# 2x_Rollo_APP_TS_v0_1.net
KiCad netlist of a schematic drawn in EAGLE
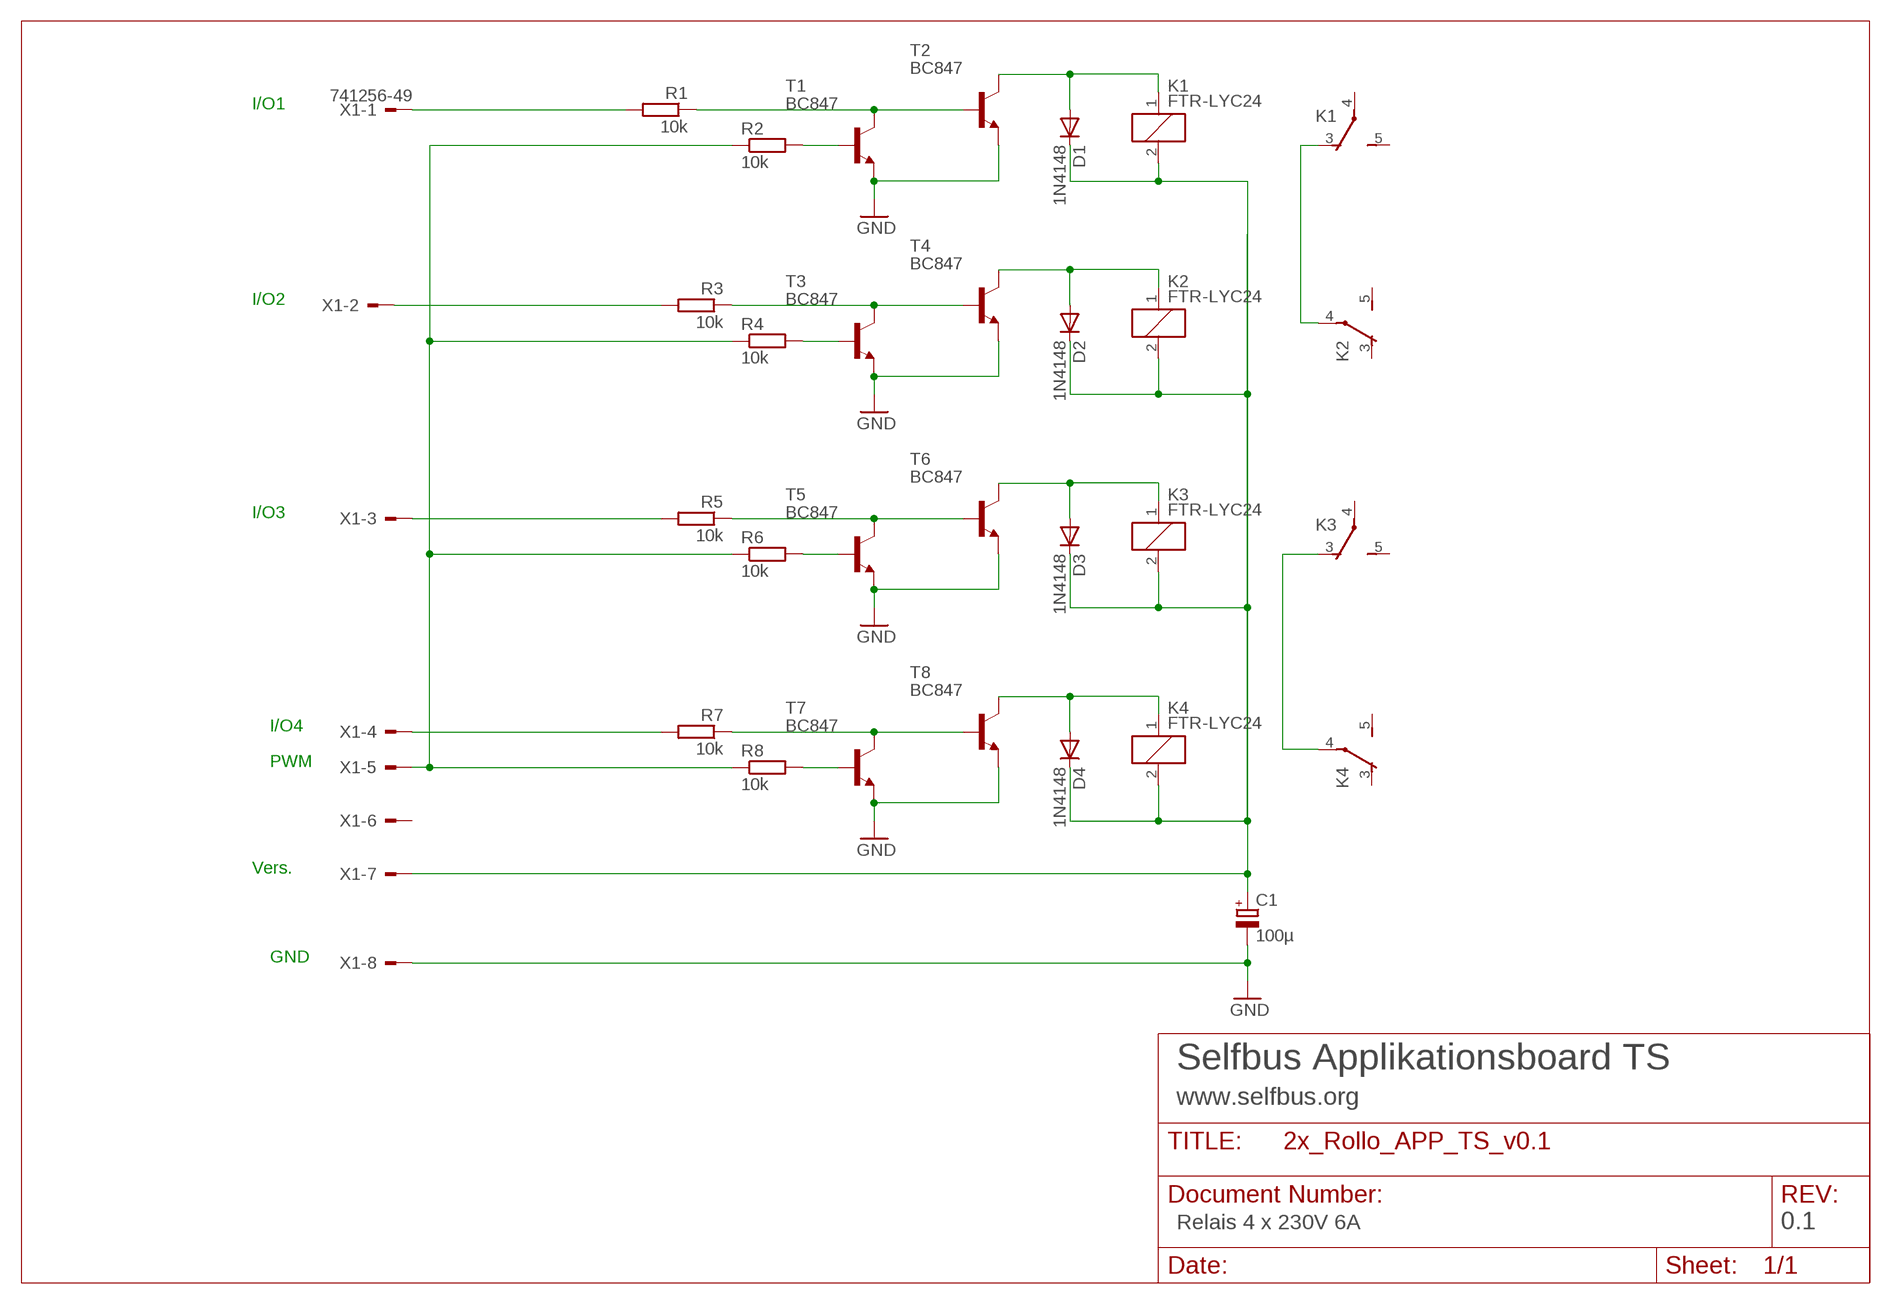
[diagram p0: schematic, sheet 1]

(export (version "E")
  (design (tool "Eeschema 10.0.6"))
  (components
    (comp (ref "C1")
      (value "100µ")
      (footprint "eagle-import:E2,5-6")
      (libsource (lib "eagle-import") (part "CPOL-EUE2.5-6"))
    )
    (comp (ref "D1")
      (value "1N4148")
      (footprint "eagle-import:MINIMELF")
      (libsource (lib "eagle-import") (part "DIODE-MINIMELF"))
    )
    (comp (ref "D2")
      (value "1N4148")
      (footprint "eagle-import:MINIMELF")
      (libsource (lib "eagle-import") (part "DIODE-MINIMELF"))
    )
    (comp (ref "D3")
      (value "1N4148")
      (footprint "eagle-import:MINIMELF")
      (libsource (lib "eagle-import") (part "DIODE-MINIMELF"))
    )
    (comp (ref "D4")
      (value "1N4148")
      (footprint "eagle-import:MINIMELF")
      (libsource (lib "eagle-import") (part "DIODE-MINIMELF"))
    )
    (comp (ref "K1")
      (value "FTR-LYC24")
      (footprint "eagle-import:FTR-LYC")
      (libsource (lib "eagle-import") (part "FTR-LYC24"))
    )
    (comp (ref "K2")
      (value "FTR-LYC24")
      (footprint "eagle-import:FTR-LYC")
      (libsource (lib "eagle-import") (part "FTR-LYC24"))
    )
    (comp (ref "K3")
      (value "FTR-LYC24")
      (footprint "eagle-import:FTR-LYC")
      (libsource (lib "eagle-import") (part "FTR-LYC24"))
    )
    (comp (ref "K4")
      (value "FTR-LYC24")
      (footprint "eagle-import:FTR-LYC")
      (libsource (lib "eagle-import") (part "FTR-LYC24"))
    )
    (comp (ref "R1")
      (value "10k")
      (footprint "eagle-import:M1206")
      (libsource (lib "eagle-import") (part "R-EU_M1206"))
    )
    (comp (ref "R2")
      (value "10k")
      (footprint "eagle-import:M1206")
      (libsource (lib "eagle-import") (part "R-EU_M1206"))
    )
    (comp (ref "R3")
      (value "10k")
      (footprint "eagle-import:M1206")
      (libsource (lib "eagle-import") (part "R-EU_M1206"))
    )
    (comp (ref "R4")
      (value "10k")
      (footprint "eagle-import:M1206")
      (libsource (lib "eagle-import") (part "R-EU_M1206"))
    )
    (comp (ref "R5")
      (value "10k")
      (footprint "eagle-import:M1206")
      (libsource (lib "eagle-import") (part "R-EU_M1206"))
    )
    (comp (ref "R6")
      (value "10k")
      (footprint "eagle-import:M1206")
      (libsource (lib "eagle-import") (part "R-EU_M1206"))
    )
    (comp (ref "R7")
      (value "10k")
      (footprint "eagle-import:M1206")
      (libsource (lib "eagle-import") (part "R-EU_M1206"))
    )
    (comp (ref "R8")
      (value "10k")
      (footprint "eagle-import:M1206")
      (libsource (lib "eagle-import") (part "R-EU_M1206"))
    )
    (comp (ref "T1")
      (value "BC847")
      (footprint "eagle-import:SOT23")
      (libsource (lib "eagle-import") (part "BC847"))
    )
    (comp (ref "T2")
      (value "BC847")
      (footprint "eagle-import:SOT23")
      (libsource (lib "eagle-import") (part "BC847"))
    )
    (comp (ref "T3")
      (value "BC847")
      (footprint "eagle-import:SOT23")
      (libsource (lib "eagle-import") (part "BC847"))
    )
    (comp (ref "T4")
      (value "BC847")
      (footprint "eagle-import:SOT23")
      (libsource (lib "eagle-import") (part "BC847"))
    )
    (comp (ref "T5")
      (value "BC847")
      (footprint "eagle-import:SOT23")
      (libsource (lib "eagle-import") (part "BC847"))
    )
    (comp (ref "T6")
      (value "BC847")
      (footprint "eagle-import:SOT23")
      (libsource (lib "eagle-import") (part "BC847"))
    )
    (comp (ref "T7")
      (value "BC847")
      (footprint "eagle-import:SOT23")
      (libsource (lib "eagle-import") (part "BC847"))
    )
    (comp (ref "T8")
      (value "BC847")
      (footprint "eagle-import:SOT23")
      (libsource (lib "eagle-import") (part "BC847"))
    )
    (comp (ref "X1")
      (value "741256-49")
      (footprint "eagle-import:741256-49")
      (libsource (lib "eagle-import") (part "741256-49"))
    )
  )
  (nets
    (net (code "1") (name "GND") (class "Default")
      (node (ref "C1") (pin "-") (pinfunction "-_-") (pintype "passive"))
      (node (ref "T1") (pin "2") (pinfunction "E_2") (pintype "passive"))
      (node (ref "T2") (pin "2") (pinfunction "E_2") (pintype "passive"))
      (node (ref "T3") (pin "2") (pinfunction "E_2") (pintype "passive"))
      (node (ref "T4") (pin "2") (pinfunction "E_2") (pintype "passive"))
      (node (ref "T5") (pin "2") (pinfunction "E_2") (pintype "passive"))
      (node (ref "T6") (pin "2") (pinfunction "E_2") (pintype "passive"))
      (node (ref "T7") (pin "2") (pinfunction "E_2") (pintype "passive"))
      (node (ref "T8") (pin "2") (pinfunction "E_2") (pintype "passive"))
      (node (ref "X1") (pin "8") (pinfunction "KL_8") (pintype "passive"))
    )
    (net (code "2") (name "Net-(K1A-O)") (class "Default")
      (node (ref "K1") (pin "3") (pinfunction "O_3") (pintype "passive"))
      (node (ref "K2") (pin "4") (pinfunction "P_4") (pintype "passive"))
    )
    (net (code "3") (name "Net-(K3A-O)") (class "Default")
      (node (ref "K3") (pin "3") (pinfunction "O_3") (pintype "passive"))
      (node (ref "K4") (pin "4") (pinfunction "P_4") (pintype "passive"))
    )
    (net (code "4") (name "Net-(T1-B)") (class "Default")
      (node (ref "R2") (pin "2") (pinfunction "2_2") (pintype "passive"))
      (node (ref "T1") (pin "1") (pinfunction "B_1") (pintype "passive"))
    )
    (net (code "5") (name "Net-(T1-C)") (class "Default")
      (node (ref "R1") (pin "1") (pinfunction "1_1") (pintype "passive"))
      (node (ref "T1") (pin "3") (pinfunction "C_3") (pintype "passive"))
      (node (ref "T2") (pin "1") (pinfunction "B_1") (pintype "passive"))
    )
    (net (code "6") (name "Net-(T2-C)") (class "Default")
      (node (ref "D1") (pin "A") (pinfunction "A_A") (pintype "passive"))
      (node (ref "K1") (pin "1") (pinfunction "1_1") (pintype "passive"))
      (node (ref "T2") (pin "3") (pinfunction "C_3") (pintype "passive"))
    )
    (net (code "7") (name "Net-(T3-B)") (class "Default")
      (node (ref "R4") (pin "2") (pinfunction "2_2") (pintype "passive"))
      (node (ref "T3") (pin "1") (pinfunction "B_1") (pintype "passive"))
    )
    (net (code "8") (name "Net-(T3-C)") (class "Default")
      (node (ref "R3") (pin "1") (pinfunction "1_1") (pintype "passive"))
      (node (ref "T3") (pin "3") (pinfunction "C_3") (pintype "passive"))
      (node (ref "T4") (pin "1") (pinfunction "B_1") (pintype "passive"))
    )
    (net (code "9") (name "Net-(T4-C)") (class "Default")
      (node (ref "D2") (pin "A") (pinfunction "A_A") (pintype "passive"))
      (node (ref "K2") (pin "1") (pinfunction "1_1") (pintype "passive"))
      (node (ref "T4") (pin "3") (pinfunction "C_3") (pintype "passive"))
    )
    (net (code "10") (name "Net-(T5-B)") (class "Default")
      (node (ref "R6") (pin "2") (pinfunction "2_2") (pintype "passive"))
      (node (ref "T5") (pin "1") (pinfunction "B_1") (pintype "passive"))
    )
    (net (code "11") (name "Net-(T5-C)") (class "Default")
      (node (ref "R5") (pin "1") (pinfunction "1_1") (pintype "passive"))
      (node (ref "T5") (pin "3") (pinfunction "C_3") (pintype "passive"))
      (node (ref "T6") (pin "1") (pinfunction "B_1") (pintype "passive"))
    )
    (net (code "12") (name "Net-(T6-C)") (class "Default")
      (node (ref "D3") (pin "A") (pinfunction "A_A") (pintype "passive"))
      (node (ref "K3") (pin "1") (pinfunction "1_1") (pintype "passive"))
      (node (ref "T6") (pin "3") (pinfunction "C_3") (pintype "passive"))
    )
    (net (code "13") (name "Net-(T7-B)") (class "Default")
      (node (ref "R8") (pin "2") (pinfunction "2_2") (pintype "passive"))
      (node (ref "T7") (pin "1") (pinfunction "B_1") (pintype "passive"))
    )
    (net (code "14") (name "Net-(T7-C)") (class "Default")
      (node (ref "R7") (pin "1") (pinfunction "1_1") (pintype "passive"))
      (node (ref "T7") (pin "3") (pinfunction "C_3") (pintype "passive"))
      (node (ref "T8") (pin "1") (pinfunction "B_1") (pintype "passive"))
    )
    (net (code "15") (name "Net-(T8-C)") (class "Default")
      (node (ref "D4") (pin "A") (pinfunction "A_A") (pintype "passive"))
      (node (ref "K4") (pin "1") (pinfunction "1_1") (pintype "passive"))
      (node (ref "T8") (pin "3") (pinfunction "C_3") (pintype "passive"))
    )
    (net (code "16") (name "Net-(X1A-KL)") (class "Default")
      (node (ref "R1") (pin "2") (pinfunction "2_2") (pintype "passive"))
      (node (ref "X1") (pin "1") (pinfunction "KL_1") (pintype "passive"))
    )
    (net (code "17") (name "Net-(X1B-KL)") (class "Default")
      (node (ref "R3") (pin "2") (pinfunction "2_2") (pintype "passive"))
      (node (ref "X1") (pin "2") (pinfunction "KL_2") (pintype "passive"))
    )
    (net (code "18") (name "Net-(X1C-KL)") (class "Default")
      (node (ref "R5") (pin "2") (pinfunction "2_2") (pintype "passive"))
      (node (ref "X1") (pin "3") (pinfunction "KL_3") (pintype "passive"))
    )
    (net (code "19") (name "Net-(X1D-KL)") (class "Default")
      (node (ref "R7") (pin "2") (pinfunction "2_2") (pintype "passive"))
      (node (ref "X1") (pin "4") (pinfunction "KL_4") (pintype "passive"))
    )
    (net (code "20") (name "Net-(X1E-KL)") (class "Default")
      (node (ref "R2") (pin "1") (pinfunction "1_1") (pintype "passive"))
      (node (ref "R4") (pin "1") (pinfunction "1_1") (pintype "passive"))
      (node (ref "R6") (pin "1") (pinfunction "1_1") (pintype "passive"))
      (node (ref "R8") (pin "1") (pinfunction "1_1") (pintype "passive"))
      (node (ref "X1") (pin "5") (pinfunction "KL_5") (pintype "passive"))
    )
    (net (code "21") (name "Net-(X1G-KL)") (class "Default")
      (node (ref "C1") (pin "+") (pinfunction "+_+") (pintype "passive"))
      (node (ref "D1") (pin "C") (pinfunction "C_C") (pintype "passive"))
      (node (ref "D2") (pin "C") (pinfunction "C_C") (pintype "passive"))
      (node (ref "D3") (pin "C") (pinfunction "C_C") (pintype "passive"))
      (node (ref "D4") (pin "C") (pinfunction "C_C") (pintype "passive"))
      (node (ref "K1") (pin "2") (pinfunction "2_2") (pintype "passive"))
      (node (ref "K2") (pin "2") (pinfunction "2_2") (pintype "passive"))
      (node (ref "K3") (pin "2") (pinfunction "2_2") (pintype "passive"))
      (node (ref "K4") (pin "2") (pinfunction "2_2") (pintype "passive"))
      (node (ref "X1") (pin "7") (pinfunction "KL_7") (pintype "passive"))
    )
    (net (code "22") (name "unconnected-(K1A-P-Pad4)") (class "Default")
      (node (ref "K1") (pin "4") (pinfunction "P_4") (pintype "passive"))
    )
    (net (code "23") (name "unconnected-(K1A-S-Pad5)") (class "Default")
      (node (ref "K1") (pin "5") (pinfunction "S_5") (pintype "passive"))
    )
    (net (code "24") (name "unconnected-(K2A-O-Pad3)") (class "Default")
      (node (ref "K2") (pin "3") (pinfunction "O_3") (pintype "passive"))
    )
    (net (code "25") (name "unconnected-(K2A-S-Pad5)") (class "Default")
      (node (ref "K2") (pin "5") (pinfunction "S_5") (pintype "passive"))
    )
    (net (code "26") (name "unconnected-(K3A-P-Pad4)") (class "Default")
      (node (ref "K3") (pin "4") (pinfunction "P_4") (pintype "passive"))
    )
    (net (code "27") (name "unconnected-(K3A-S-Pad5)") (class "Default")
      (node (ref "K3") (pin "5") (pinfunction "S_5") (pintype "passive"))
    )
    (net (code "28") (name "unconnected-(K4A-O-Pad3)") (class "Default")
      (node (ref "K4") (pin "3") (pinfunction "O_3") (pintype "passive"))
    )
    (net (code "29") (name "unconnected-(K4A-S-Pad5)") (class "Default")
      (node (ref "K4") (pin "5") (pinfunction "S_5") (pintype "passive"))
    )
    (net (code "30") (name "unconnected-(X1F-KL-Pad6)") (class "Default")
      (node (ref "X1") (pin "6") (pinfunction "KL_6") (pintype "passive"))
    )
  )
)
